# Rev1.net
KiCad netlist of a schematic drawn in EAGLE
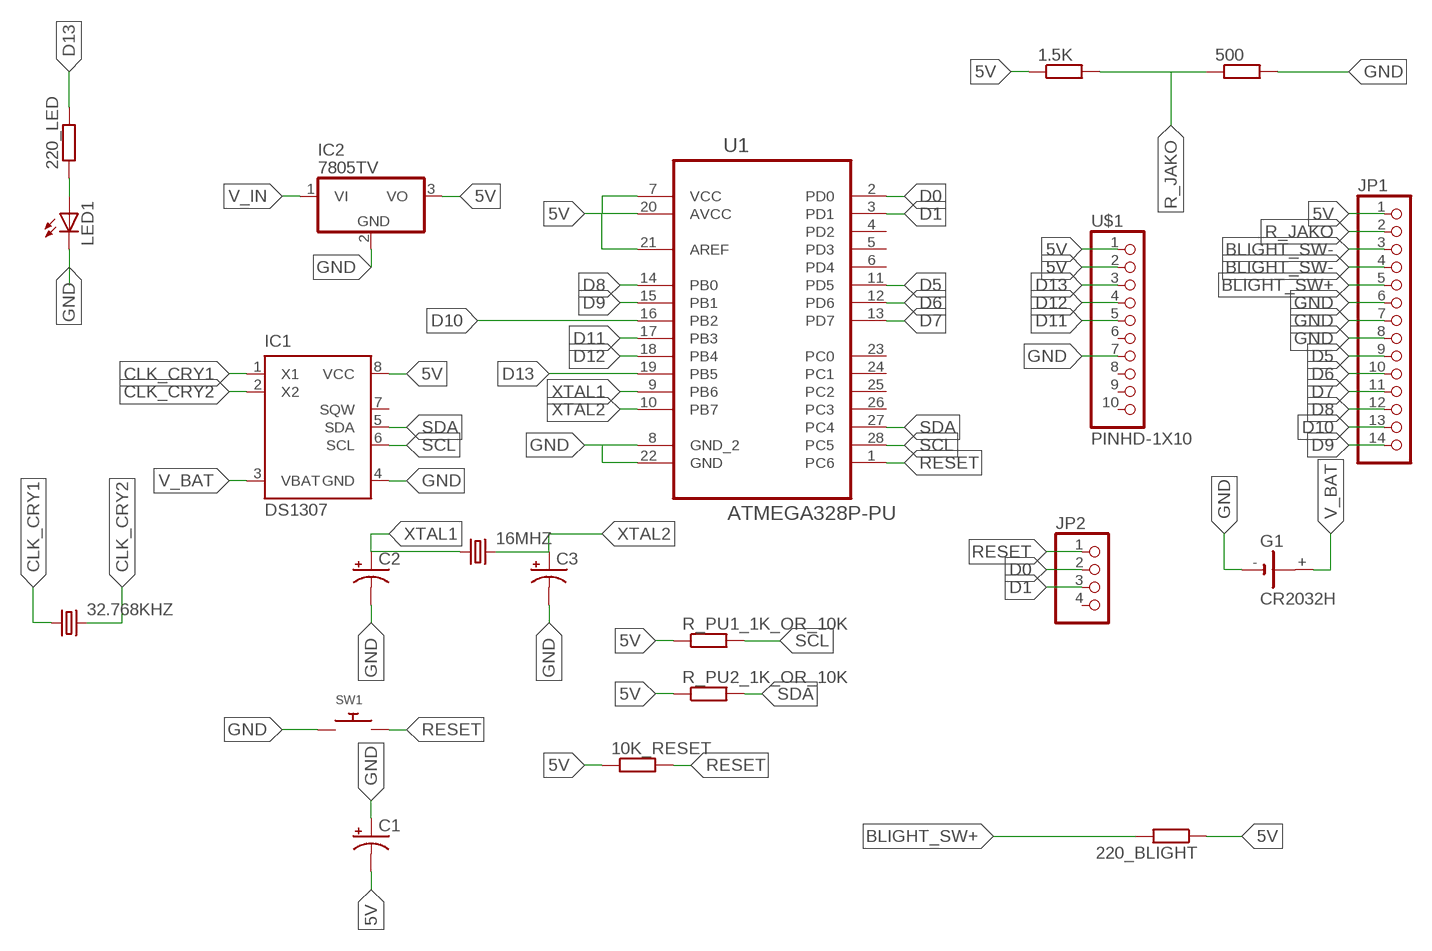
[diagram p0: schematic, sheet 1]

(export (version "E")
  (design (tool "Eeschema 10.0.6"))
  (components
    (comp (ref "1.5K")
      (value "R-EU_0207/10")
      (footprint "eagle-import:0207_10")
      (libsource (lib "eagle-import") (part "R-EU_0207/10"))
    )
    (comp (ref "10K_RESET")
      (value "R-EU_0207/10")
      (footprint "eagle-import:0207_10")
      (libsource (lib "eagle-import") (part "R-EU_0207/10"))
    )
    (comp (ref "16MHZ")
      (value "CRYSTALHC49S")
      (footprint "eagle-import:HC49_S")
      (libsource (lib "eagle-import") (part "CRYSTALHC49S"))
    )
    (comp (ref "32.768KHZ")
      (value "CRYSTALTC38H")
      (footprint "eagle-import:TC38H")
      (libsource (lib "eagle-import") (part "CRYSTALTC38H"))
    )
    (comp (ref "220_BLIGHT")
      (value "R-EU_0207/10")
      (footprint "eagle-import:0207_10")
      (libsource (lib "eagle-import") (part "R-EU_0207/10"))
    )
    (comp (ref "220_LED")
      (value "R-EU_0207/10")
      (footprint "eagle-import:0207_10")
      (libsource (lib "eagle-import") (part "R-EU_0207/10"))
    )
    (comp (ref "500")
      (value "R-EU_0207/10")
      (footprint "eagle-import:0207_10")
      (libsource (lib "eagle-import") (part "R-EU_0207/10"))
    )
    (comp (ref "C1")
      (value "CPOL-USE2,5-6E")
      (footprint "eagle-import:E2,5-6E")
      (libsource (lib "eagle-import") (part "CPOL-USE2,5-6E"))
    )
    (comp (ref "C2")
      (value "CPOL-USE2,5-6E")
      (footprint "eagle-import:E2,5-6E")
      (libsource (lib "eagle-import") (part "CPOL-USE2,5-6E"))
    )
    (comp (ref "C3")
      (value "CPOL-USE2,5-6E")
      (footprint "eagle-import:E2,5-6E")
      (libsource (lib "eagle-import") (part "CPOL-USE2,5-6E"))
    )
    (comp (ref "G1")
      (value "CR2032H")
      (footprint "eagle-import:CR2032H")
      (libsource (lib "eagle-import") (part "CR2032H"))
    )
    (comp (ref "IC1")
      (value "DS1307")
      (footprint "eagle-import:DIP-8")
      (libsource (lib "eagle-import") (part "DS1307"))
    )
    (comp (ref "IC2")
      (value "7805TV")
      (footprint "eagle-import:TO220V")
      (libsource (lib "eagle-import") (part "78TV05"))
    )
    (comp (ref "JP1")
      (value "PINHD-1X14")
      (footprint "eagle-import:1X14")
      (libsource (lib "eagle-import") (part "PINHD-1X14"))
    )
    (comp (ref "JP2")
      (value "PINHD-1X4")
      (footprint "eagle-import:1X04")
      (libsource (lib "eagle-import") (part "PINHD-1X4"))
    )
    (comp (ref "LED1")
      (value "LED3MM")
      (footprint "eagle-import:LED3MM")
      (libsource (lib "eagle-import") (part "LED3MM"))
    )
    (comp (ref "R_PU1_1K_OR_10K")
      (value "R-EU_0207/10")
      (footprint "eagle-import:0207_10")
      (libsource (lib "eagle-import") (part "R-EU_0207/10"))
    )
    (comp (ref "R_PU2_1K_OR_10K")
      (value "R-EU_0207/10")
      (footprint "eagle-import:0207_10")
      (libsource (lib "eagle-import") (part "R-EU_0207/10"))
    )
    (comp (ref "SW1")
      (value "SWITCH_PUSHBUTTONEVQ-PE")
      (footprint "eagle-import:TACT_PANA-EVQ")
      (libsource (lib "eagle-import") (part "SWITCH_PUSHBUTTONEVQ-PE"))
    )
    (comp (ref "U$1")
      (value "PINHD-1X10")
      (footprint "eagle-import:1X10-BIG")
      (libsource (lib "eagle-import") (part "PINHD-1X10"))
    )
    (comp (ref "U1")
      (value "ATMEGA328P-PU")
      (footprint "eagle-import:DIP254P762X457-28")
      (libsource (lib "eagle-import") (part "ATMEGA328P-PU"))
    )
  )
  (nets
    (net (code "1") (name "5V") (class "Default")
      (node (ref "1.5K") (pin "1") (pinfunction "1_1") (pintype "passive"))
      (node (ref "10K_RESET") (pin "1") (pinfunction "1_1") (pintype "passive"))
      (node (ref "220_BLIGHT") (pin "1") (pinfunction "1_1") (pintype "passive"))
      (node (ref "C1") (pin "-") (pinfunction "-_-") (pintype "passive"))
      (node (ref "IC1") (pin "8") (pinfunction "VCC_8") (pintype "power_in"))
      (node (ref "IC2") (pin "3") (pinfunction "VO_3") (pintype "passive"))
      (node (ref "JP1") (pin "1") (pinfunction "1_1") (pintype "passive"))
      (node (ref "R_PU1_1K_OR_10K") (pin "1") (pinfunction "1_1") (pintype "passive"))
      (node (ref "R_PU2_1K_OR_10K") (pin "1") (pinfunction "1_1") (pintype "passive"))
      (node (ref "U$1") (pin "1") (pinfunction "1_1") (pintype "passive"))
      (node (ref "U$1") (pin "2") (pinfunction "2_2") (pintype "passive"))
      (node (ref "U1") (pin "20") (pinfunction "AVCC_20") (pintype "power_in"))
      (node (ref "U1") (pin "21") (pinfunction "AREF_21") (pintype "input"))
      (node (ref "U1") (pin "7") (pinfunction "VCC_7") (pintype "power_in"))
    )
    (net (code "2") (name "BLIGHT_SW+") (class "Default")
      (node (ref "220_BLIGHT") (pin "2") (pinfunction "2_2") (pintype "passive"))
      (node (ref "JP1") (pin "5") (pinfunction "5_5") (pintype "passive"))
    )
    (net (code "3") (name "BLIGHT_SW-") (class "Default")
      (node (ref "JP1") (pin "3") (pinfunction "3_3") (pintype "passive"))
      (node (ref "JP1") (pin "4") (pinfunction "4_4") (pintype "passive"))
    )
    (net (code "4") (name "CLK_CRY1") (class "Default")
      (node (ref "32.768KHZ") (pin "1") (pinfunction "1_1") (pintype "passive"))
      (node (ref "IC1") (pin "1") (pinfunction "X1_1") (pintype "input"))
    )
    (net (code "5") (name "CLK_CRY2") (class "Default")
      (node (ref "32.768KHZ") (pin "2") (pinfunction "2_2") (pintype "passive"))
      (node (ref "IC1") (pin "2") (pinfunction "X2_2") (pintype "input"))
    )
    (net (code "6") (name "D0") (class "Default")
      (node (ref "JP2") (pin "2") (pinfunction "2_2") (pintype "passive"))
      (node (ref "U1") (pin "2") (pinfunction "PD0_2") (pintype "bidirectional"))
    )
    (net (code "7") (name "D1") (class "Default")
      (node (ref "JP2") (pin "3") (pinfunction "3_3") (pintype "passive"))
      (node (ref "U1") (pin "3") (pinfunction "PD1_3") (pintype "bidirectional"))
    )
    (net (code "8") (name "D5") (class "Default")
      (node (ref "JP1") (pin "9") (pinfunction "9_9") (pintype "passive"))
      (node (ref "U1") (pin "11") (pinfunction "PD5_11") (pintype "bidirectional"))
    )
    (net (code "9") (name "D6") (class "Default")
      (node (ref "JP1") (pin "10") (pinfunction "10_10") (pintype "passive"))
      (node (ref "U1") (pin "12") (pinfunction "PD6_12") (pintype "bidirectional"))
    )
    (net (code "10") (name "D7") (class "Default")
      (node (ref "JP1") (pin "11") (pinfunction "11_11") (pintype "passive"))
      (node (ref "U1") (pin "13") (pinfunction "PD7_13") (pintype "bidirectional"))
    )
    (net (code "11") (name "D8") (class "Default")
      (node (ref "JP1") (pin "12") (pinfunction "12_12") (pintype "passive"))
      (node (ref "U1") (pin "14") (pinfunction "PB0_14") (pintype "bidirectional"))
    )
    (net (code "12") (name "D9") (class "Default")
      (node (ref "JP1") (pin "14") (pinfunction "14_14") (pintype "passive"))
      (node (ref "U1") (pin "15") (pinfunction "PB1_15") (pintype "bidirectional"))
    )
    (net (code "13") (name "D10") (class "Default")
      (node (ref "JP1") (pin "13") (pinfunction "13_13") (pintype "passive"))
      (node (ref "U1") (pin "16") (pinfunction "PB2_16") (pintype "bidirectional"))
    )
    (net (code "14") (name "D11") (class "Default")
      (node (ref "U$1") (pin "5") (pinfunction "5_5") (pintype "passive"))
      (node (ref "U1") (pin "17") (pinfunction "PB3_17") (pintype "bidirectional"))
    )
    (net (code "15") (name "D12") (class "Default")
      (node (ref "U$1") (pin "4") (pinfunction "4_4") (pintype "passive"))
      (node (ref "U1") (pin "18") (pinfunction "PB4_18") (pintype "bidirectional"))
    )
    (net (code "16") (name "D13") (class "Default")
      (node (ref "220_LED") (pin "2") (pinfunction "2_2") (pintype "passive"))
      (node (ref "U$1") (pin "3") (pinfunction "3_3") (pintype "passive"))
      (node (ref "U1") (pin "19") (pinfunction "PB5_19") (pintype "bidirectional"))
    )
    (net (code "17") (name "GND") (class "Default")
      (node (ref "500") (pin "2") (pinfunction "2_2") (pintype "passive"))
      (node (ref "C1") (pin "+") (pinfunction "+_+") (pintype "passive"))
      (node (ref "C2") (pin "-") (pinfunction "-_-") (pintype "passive"))
      (node (ref "C3") (pin "-") (pinfunction "-_-") (pintype "passive"))
      (node (ref "G1") (pin "-") (pinfunction "-_-") (pintype "passive"))
      (node (ref "IC1") (pin "4") (pinfunction "GND_4") (pintype "power_in"))
      (node (ref "IC2") (pin "2") (pinfunction "GND_2") (pintype "passive"))
      (node (ref "JP1") (pin "6") (pinfunction "6_6") (pintype "passive"))
      (node (ref "JP1") (pin "7") (pinfunction "7_7") (pintype "passive"))
      (node (ref "JP1") (pin "8") (pinfunction "8_8") (pintype "passive"))
      (node (ref "LED1") (pin "K") (pinfunction "C_K") (pintype "passive"))
      (node (ref "SW1") (pin "P$1") (pinfunction "P$1_P$1") (pintype "passive"))
      (node (ref "U$1") (pin "7") (pinfunction "7_7") (pintype "passive"))
      (node (ref "U1") (pin "22") (pinfunction "GND_22") (pintype "passive"))
      (node (ref "U1") (pin "8") (pinfunction "GND_2_8") (pintype "passive"))
    )
    (net (code "18") (name "Net-(220_LED-Pad1)") (class "Default")
      (node (ref "220_LED") (pin "1") (pinfunction "1_1") (pintype "passive"))
      (node (ref "LED1") (pin "A") (pinfunction "A_A") (pintype "passive"))
    )
    (net (code "19") (name "RESET") (class "Default")
      (node (ref "10K_RESET") (pin "2") (pinfunction "2_2") (pintype "passive"))
      (node (ref "JP2") (pin "1") (pinfunction "1_1") (pintype "passive"))
      (node (ref "SW1") (pin "P$2") (pinfunction "P$2_P$2") (pintype "passive"))
      (node (ref "U1") (pin "1") (pinfunction "PC6_1") (pintype "bidirectional"))
    )
    (net (code "20") (name "R_JAKO") (class "Default")
      (node (ref "1.5K") (pin "2") (pinfunction "2_2") (pintype "passive"))
      (node (ref "500") (pin "1") (pinfunction "1_1") (pintype "passive"))
      (node (ref "JP1") (pin "2") (pinfunction "2_2") (pintype "passive"))
    )
    (net (code "21") (name "SCL") (class "Default")
      (node (ref "IC1") (pin "6") (pinfunction "SCL_6") (pintype "input"))
      (node (ref "R_PU1_1K_OR_10K") (pin "2") (pinfunction "2_2") (pintype "passive"))
      (node (ref "U1") (pin "28") (pinfunction "PC5_28") (pintype "bidirectional"))
    )
    (net (code "22") (name "SDA") (class "Default")
      (node (ref "IC1") (pin "5") (pinfunction "SDA_5") (pintype "output"))
      (node (ref "R_PU2_1K_OR_10K") (pin "2") (pinfunction "2_2") (pintype "passive"))
      (node (ref "U1") (pin "27") (pinfunction "PC4_27") (pintype "bidirectional"))
    )
    (net (code "23") (name "V_BAT") (class "Default")
      (node (ref "G1") (pin "+") (pinfunction "+_+") (pintype "passive"))
      (node (ref "IC1") (pin "3") (pinfunction "VBAT_3") (pintype "input"))
    )
    (net (code "24") (name "V_IN") (class "Default")
      (node (ref "IC2") (pin "1") (pinfunction "VI_1") (pintype "input"))
    )
    (net (code "25") (name "XTAL1") (class "Default")
      (node (ref "16MHZ") (pin "1") (pinfunction "1_1") (pintype "passive"))
      (node (ref "C2") (pin "+") (pinfunction "+_+") (pintype "passive"))
      (node (ref "U1") (pin "9") (pinfunction "PB6_9") (pintype "bidirectional"))
    )
    (net (code "26") (name "XTAL2") (class "Default")
      (node (ref "16MHZ") (pin "2") (pinfunction "2_2") (pintype "passive"))
      (node (ref "C3") (pin "+") (pinfunction "+_+") (pintype "passive"))
      (node (ref "U1") (pin "10") (pinfunction "PB7_10") (pintype "bidirectional"))
    )
    (net (code "27") (name "unconnected-(G1-+-Pad+@1)") (class "Default")
      (node (ref "G1") (pin "+@1") (pinfunction "+_+@1") (pintype "passive"))
    )
    (net (code "28") (name "unconnected-(IC1-SQW-Pad7)") (class "Default")
      (node (ref "IC1") (pin "7") (pinfunction "SQW_7") (pintype "input"))
    )
    (net (code "29") (name "unconnected-(JP2-Pad4)") (class "Default")
      (node (ref "JP2") (pin "4") (pinfunction "4_4") (pintype "passive"))
    )
    (net (code "30") (name "unconnected-(U$1-Pad6)") (class "Default")
      (node (ref "U$1") (pin "6") (pinfunction "6_6") (pintype "passive"))
    )
    (net (code "31") (name "unconnected-(U$1-Pad8)") (class "Default")
      (node (ref "U$1") (pin "8") (pinfunction "8_8") (pintype "passive"))
    )
    (net (code "32") (name "unconnected-(U$1-Pad9)") (class "Default")
      (node (ref "U$1") (pin "9") (pinfunction "9_9") (pintype "passive"))
    )
    (net (code "33") (name "unconnected-(U$1-Pad10)") (class "Default")
      (node (ref "U$1") (pin "10") (pinfunction "10_10") (pintype "passive"))
    )
    (net (code "34") (name "unconnected-(U1-PC0-Pad23)") (class "Default")
      (node (ref "U1") (pin "23") (pinfunction "PC0_23") (pintype "bidirectional"))
    )
    (net (code "35") (name "unconnected-(U1-PC1-Pad24)") (class "Default")
      (node (ref "U1") (pin "24") (pinfunction "PC1_24") (pintype "bidirectional"))
    )
    (net (code "36") (name "unconnected-(U1-PC2-Pad25)") (class "Default")
      (node (ref "U1") (pin "25") (pinfunction "PC2_25") (pintype "bidirectional"))
    )
    (net (code "37") (name "unconnected-(U1-PC3-Pad26)") (class "Default")
      (node (ref "U1") (pin "26") (pinfunction "PC3_26") (pintype "bidirectional"))
    )
    (net (code "38") (name "unconnected-(U1-PD2-Pad4)") (class "Default")
      (node (ref "U1") (pin "4") (pinfunction "PD2_4") (pintype "bidirectional"))
    )
    (net (code "39") (name "unconnected-(U1-PD3-Pad5)") (class "Default")
      (node (ref "U1") (pin "5") (pinfunction "PD3_5") (pintype "bidirectional"))
    )
    (net (code "40") (name "unconnected-(U1-PD4-Pad6)") (class "Default")
      (node (ref "U1") (pin "6") (pinfunction "PD4_6") (pintype "bidirectional"))
    )
  )
)
